# PFC_control_board.net
KiCad netlist of a schematic drawn in Altium Designer
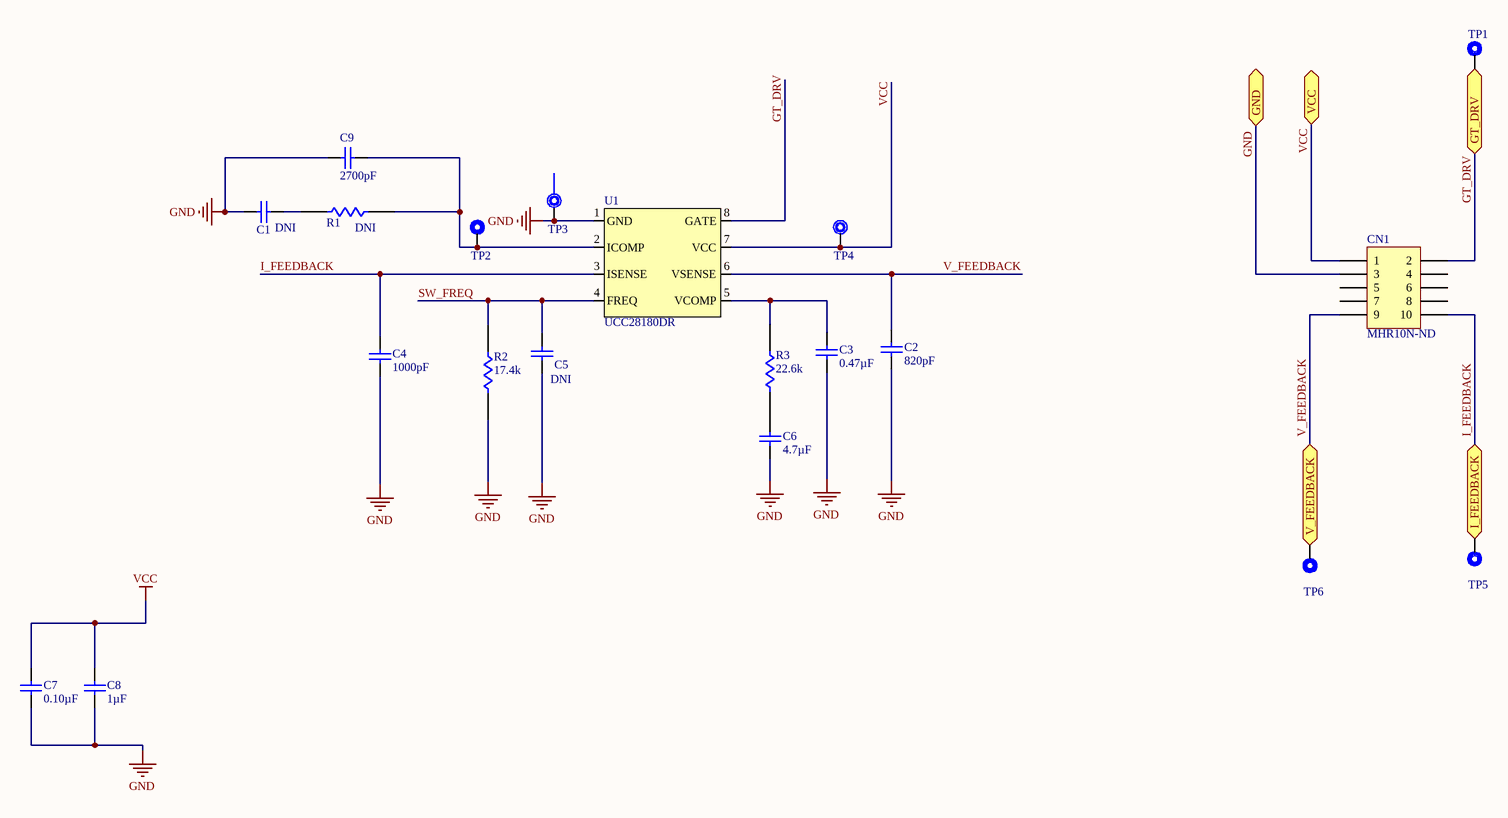
[diagram p0: PFC control board.SchDoc]

(export (version "E")
  (design (tool "Eeschema 10.0.6"))
  (components
    (comp (ref "C1")
      (value "C0603--")
      (footprint "CAP0603")
      (libsource (lib "ucc28180-V03") (part "C0603--"))
    )
    (comp (ref "C2")
      (value "C0603C821K5RACTU")
      (footprint "CAP0603")
      (description "CAP CER 820PF 50V X7R 0603")
      (fields (field (name "TOLERANCE") "±10%") (field (name "CAPACITANCE") "820pF"))
      (libsource (lib "ucc28180-V03") (part "C0603C821K5RACTU"))
    )
    (comp (ref "C3")
      (value "C0603C474K4RACTU")
      (footprint "CAP0603")
      (description "CAP CER 0.47UF 16V X7R 0603")
      (fields (field (name "TOLERANCE") "±10%") (field (name "CAPACITANCE") "0.47µF"))
      (libsource (lib "ucc28180-V03") (part "C0603C474K4RACTU"))
    )
    (comp (ref "C4")
      (value "06031C102KAT2A")
      (footprint "CAP0603")
      (description "CAP CER 1000PF 100V X7R 0603")
      (fields (field (name "TOLERANCE") "±10%") (field (name "CAPACITANCE") "1000pF"))
      (libsource (lib "ucc28180-V03") (part "06031C102KAT2A"))
    )
    (comp (ref "C5")
      (value "C0603--")
      (footprint "CAP0603")
      (libsource (lib "ucc28180-V03") (part "C0603--"))
    )
    (comp (ref "C6")
      (value "GRM21BR71A475KA73L")
      (footprint "CAP0805")
      (description "CAP CER 4.7UF 10V X7R 0805")
      (fields (field (name "TOLERANCE") "±10%") (field (name "CAPACITANCE") "4.7µF"))
      (libsource (lib "ucc28180-V03") (part "GRM21BR71A475KA73L"))
    )
    (comp (ref "C7")
      (value "06035C104KAT2A")
      (footprint "CAP0603")
      (description "CAP CER 0.1UF 50V X7R 0603")
      (fields (field (name "TOLERANCE") "±10%") (field (name "CAPACITANCE") "0.10µF"))
      (libsource (lib "ucc28180") (part "06035C104KAT2A"))
    )
    (comp (ref "C8")
      (value "GRM32RR71H105KA01K")
      (footprint "CAP1206")
      (description "CAP CER 1UF 50V X7R 1210")
      (fields (field (name "TOLERANCE") "±10%") (field (name "CAPACITANCE") "1µF"))
      (libsource (lib "ucc28180") (part "GRM32RR71H105KA01K"))
    )
    (comp (ref "C9")
      (value "GRM188R71H272KA01D")
      (footprint "CAP0603")
      (description "CAP CER 2700PF 50V X7R 0603")
      (fields (field (name "TOLERANCE") "±10%") (field (name "CAPACITANCE") "2700pF"))
      (libsource (lib "ucc28180-V03") (part "GRM188R71H272KA01D"))
    )
    (comp (ref "CN1")
      (value "MHR10N-ND")
      (footprint "3M15452")
      (description "CONN HEADER 10PS R/A LONG LATCH")
      (fields
        (field (name "MANUFACTURER") "3M")
        (field (name "MANUFACTURER PART NUMBER") "N3793-5302RB")
        (field (name "SUPPLIER PART NUMBER 1") "MHR10N-ND")
      )
      (libsource (lib "ucc28180-V03") (part "MHR10N-ND"))
    )
    (comp (ref "R1")
      (value "CRCW0603--")
      (footprint "RES0603")
      (libsource (lib "ucc28180-V03") (part "CRCW0603--"))
    )
    (comp (ref "R2")
      (value "CRCW060317K4FKEB")
      (footprint "RES0603")
      (description "RES SMD 17.4K OHM 1% 1/10W 0603")
      (fields
        (field (name "MANUFACTURER") "Vishay Dale")
        (field (name "TOLERANCE") "±1%")
        (field (name "RESISTANCE (OHMS)") "17.4k")
      )
      (libsource (lib "ucc28180-V03") (part "CRCW060317K4FKEB"))
    )
    (comp (ref "R3")
      (value "CRCW060322K6FKEA")
      (footprint "CAP0603")
      (description "RES SMD 22.6K OHM 1% 1/10W 0603")
      (fields (field (name "TOLERANCE") "±1%") (field (name "RESISTANCE (OHMS)") "22.6k"))
      (libsource (lib "ucc28180-V03") (part "CRCW060322K6FKEA"))
    )
    (comp (ref "TP1")
      (value "5006")
      (footprint "Test Point")
      (description "TEST POINT PC COMPACT .063\"D BLK")
      (libsource (lib "ucc28180-V03") (part "5006"))
    )
    (comp (ref "TP2")
      (value "5006")
      (footprint "Test Point")
      (description "TEST POINT PC COMPACT .063\"D BLK")
      (libsource (lib "ucc28180-V03") (part "5006"))
    )
    (comp (ref "TP3")
      (value "TP-Slot")
      (footprint "TP-Slot")
      (libsource (lib "ucc28180-V03") (part "TP-Slot"))
    )
    (comp (ref "TP4") (value "TP-SM") (footprint "TP-SM") (libsource (lib "ucc28180-V03") (part "TP-SM")))
    (comp (ref "TP5")
      (value "5006")
      (footprint "Test Point")
      (description "TEST POINT PC COMPACT .063\"D BLK")
      (libsource (lib "ucc28180-V03") (part "5006"))
    )
    (comp (ref "TP6")
      (value "5006")
      (footprint "Test Point")
      (description "TEST POINT PC COMPACT .063\"D BLK")
      (libsource (lib "ucc28180-V03") (part "5006"))
    )
    (comp (ref "U1")
      (value "UCC28180DR")
      (footprint "SOP127P600X175-8N")
      (description "IC PFC CTRLR AVERAGE CURR 8SOIC")
      (libsource (lib "ucc28180-V03") (part "UCC28180DR"))
    )
  )
  (nets
    (net (code "1") (name "/GT_DRV") (class "Default")
      (node (ref "CN1") (pin "2") (pinfunction "2_2") (pintype "passive"))
      (node (ref "TP1") (pin "1") (pinfunction "1_1") (pintype "passive"))
      (node (ref "U1") (pin "8") (pinfunction "GATE_8") (pintype "passive"))
    )
    (net (code "2") (name "/I_FEEDBACK") (class "Default")
      (node (ref "C4") (pin "2") (pinfunction "2_2") (pintype "passive"))
      (node (ref "CN1") (pin "10") (pinfunction "10_10") (pintype "passive"))
      (node (ref "TP5") (pin "1") (pinfunction "1_1") (pintype "passive"))
      (node (ref "U1") (pin "3") (pinfunction "ISENSE_3") (pintype "passive"))
    )
    (net (code "3") (name "/SW_FREQ") (class "Default")
      (node (ref "C5") (pin "2") (pinfunction "2_2") (pintype "passive"))
      (node (ref "R2") (pin "1") (pinfunction "1_1") (pintype "passive"))
      (node (ref "U1") (pin "4") (pinfunction "FREQ_4") (pintype "passive"))
    )
    (net (code "4") (name "/V_FEEDBACK") (class "Default")
      (node (ref "C2") (pin "2") (pinfunction "2_2") (pintype "passive"))
      (node (ref "CN1") (pin "9") (pinfunction "9_9") (pintype "passive"))
      (node (ref "TP6") (pin "1") (pinfunction "1_1") (pintype "passive"))
      (node (ref "U1") (pin "6") (pinfunction "VSENSE_6") (pintype "passive"))
    )
    (net (code "5") (name "GND") (class "Default")
      (node (ref "C1") (pin "1") (pinfunction "1_1") (pintype "passive"))
      (node (ref "C2") (pin "1") (pinfunction "1_1") (pintype "passive"))
      (node (ref "C3") (pin "1") (pinfunction "1_1") (pintype "passive"))
      (node (ref "C4") (pin "1") (pinfunction "1_1") (pintype "passive"))
      (node (ref "C5") (pin "1") (pinfunction "1_1") (pintype "passive"))
      (node (ref "C6") (pin "1") (pinfunction "1_1") (pintype "passive"))
      (node (ref "C7") (pin "2") (pinfunction "2_2") (pintype "passive"))
      (node (ref "C8") (pin "1") (pinfunction "1_1") (pintype "passive"))
      (node (ref "C9") (pin "1") (pinfunction "1_1") (pintype "passive"))
      (node (ref "CN1") (pin "3") (pinfunction "3_3") (pintype "passive"))
      (node (ref "R2") (pin "2") (pinfunction "2_2") (pintype "passive"))
      (node (ref "TP3") (pin "1") (pinfunction "1_1") (pintype "passive"))
      (node (ref "U1") (pin "1") (pinfunction "GND_1") (pintype "passive"))
    )
    (net (code "6") (name "Net-(C1-Pad2)") (class "Default")
      (node (ref "C1") (pin "2") (pinfunction "2_2") (pintype "passive"))
      (node (ref "R1") (pin "2") (pinfunction "2_2") (pintype "passive"))
    )
    (net (code "7") (name "Net-(C6-Pad2)") (class "Default")
      (node (ref "C6") (pin "2") (pinfunction "2_2") (pintype "passive"))
      (node (ref "R3") (pin "2") (pinfunction "2_2") (pintype "passive"))
    )
    (net (code "8") (name "Net-(U1-ICOMP)") (class "Default")
      (node (ref "C9") (pin "2") (pinfunction "2_2") (pintype "passive"))
      (node (ref "R1") (pin "1") (pinfunction "1_1") (pintype "passive"))
      (node (ref "TP2") (pin "1") (pinfunction "1_1") (pintype "passive"))
      (node (ref "U1") (pin "2") (pinfunction "ICOMP_2") (pintype "passive"))
    )
    (net (code "9") (name "Net-(U1-VCOMP)") (class "Default")
      (node (ref "C3") (pin "2") (pinfunction "2_2") (pintype "passive"))
      (node (ref "R3") (pin "1") (pinfunction "1_1") (pintype "passive"))
      (node (ref "U1") (pin "5") (pinfunction "VCOMP_5") (pintype "passive"))
    )
    (net (code "10") (name "VCC") (class "Default")
      (node (ref "C7") (pin "1") (pinfunction "1_1") (pintype "passive"))
      (node (ref "C8") (pin "2") (pinfunction "2_2") (pintype "passive"))
      (node (ref "CN1") (pin "1") (pinfunction "1_1") (pintype "passive"))
      (node (ref "TP4") (pin "1") (pinfunction "1_1") (pintype "passive"))
      (node (ref "U1") (pin "7") (pinfunction "VCC_7") (pintype "passive"))
    )
    (net (code "11") (name "unconnected-(CN1-Pad4)") (class "Default")
      (node (ref "CN1") (pin "4") (pinfunction "4_4") (pintype "passive"))
    )
    (net (code "12") (name "unconnected-(CN1-Pad5)") (class "Default")
      (node (ref "CN1") (pin "5") (pinfunction "5_5") (pintype "passive"))
    )
    (net (code "13") (name "unconnected-(CN1-Pad6)") (class "Default")
      (node (ref "CN1") (pin "6") (pinfunction "6_6") (pintype "passive"))
    )
    (net (code "14") (name "unconnected-(CN1-Pad7)") (class "Default")
      (node (ref "CN1") (pin "7") (pinfunction "7_7") (pintype "passive"))
    )
    (net (code "15") (name "unconnected-(CN1-Pad8)") (class "Default")
      (node (ref "CN1") (pin "8") (pinfunction "8_8") (pintype "passive"))
    )
  )
)
